# Circlez8a.net
KiCad netlist of a schematic drawn in EAGLE
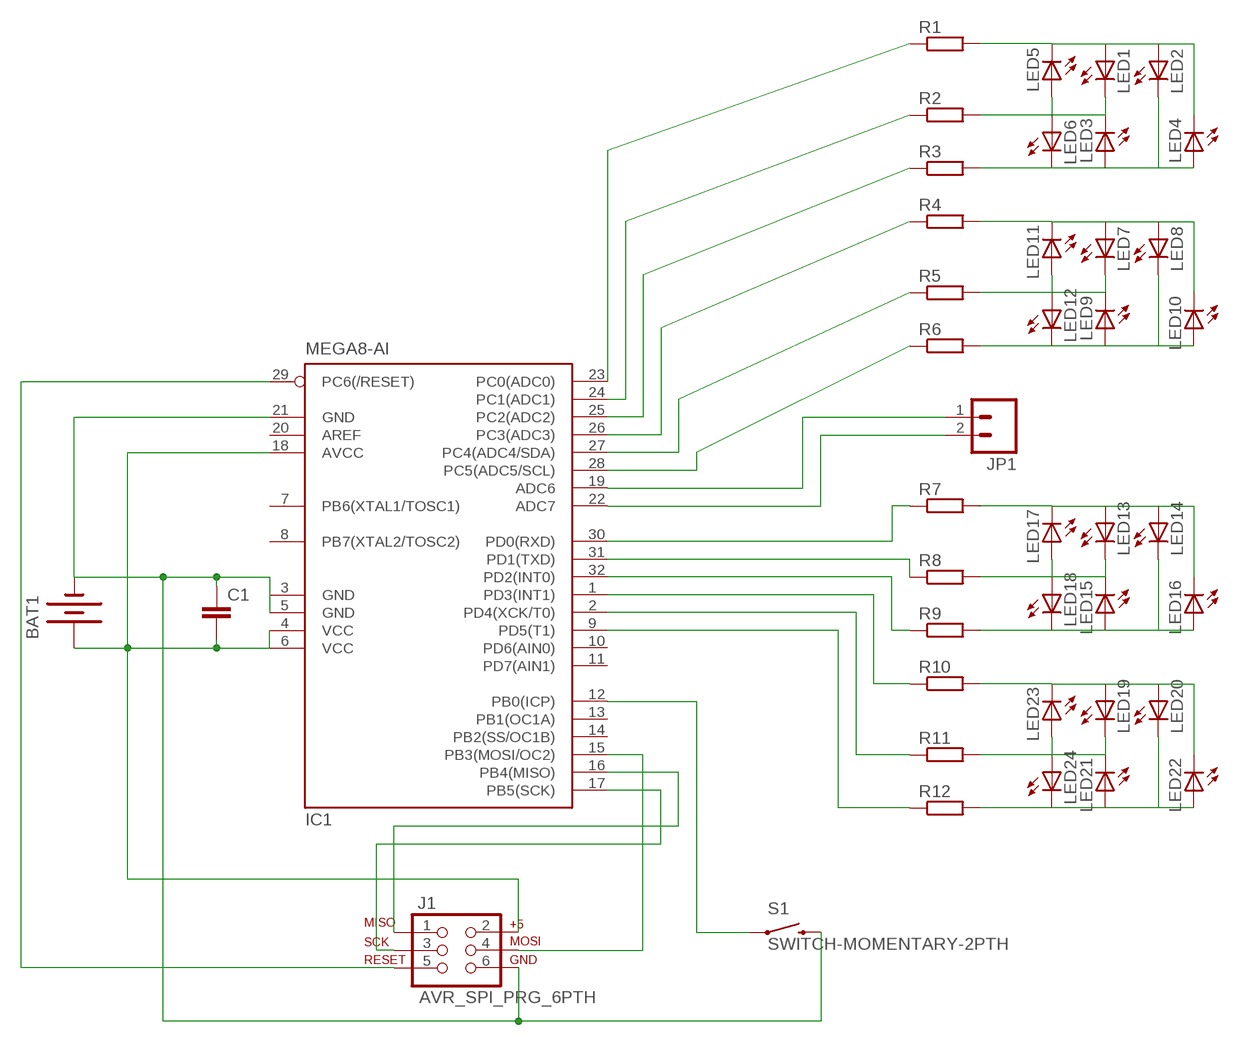
[diagram p0: schematic, sheet 1]

(export (version "E")
  (design (tool "Eeschema 10.0.6"))
  (components
    (comp (ref "BAT1")
      (value "BATTERY20PTH")
      (footprint "eagle-import:BATTCOM_20MM_PTH")
      (libsource (lib "eagle-import") (part "BATTERY20PTH"))
    )
    (comp (ref "C1")
      (value "C-EU025-024X044")
      (footprint "eagle-import:C025-024X044")
      (libsource (lib "eagle-import") (part "C-EU025-024X044"))
    )
    (comp (ref "IC1")
      (value "MEGA8-AI")
      (footprint "eagle-import:TQFP32-08")
      (fields (field (name "MPN") "ATMEGA8-16AU"))
      (libsource (lib "eagle-import") (part "MEGA8-AI"))
    )
    (comp (ref "J1")
      (value "AVR_SPI_PRG_6PTH")
      (footprint "eagle-import:2X3")
      (libsource (lib "eagle-import") (part "AVR_SPI_PRG_6PTH"))
    )
    (comp (ref "JP1")
      (value "M02PTH")
      (footprint "eagle-import:1X02")
      (libsource (lib "eagle-import") (part "M02PTH"))
    )
    (comp (ref "LED1")
      (value "LEDCHIPLED_0603")
      (footprint "eagle-import:CHIPLED_0603")
      (libsource (lib "eagle-import") (part "LEDCHIPLED_0603"))
    )
    (comp (ref "LED2")
      (value "LEDCHIPLED_0603")
      (footprint "eagle-import:CHIPLED_0603")
      (libsource (lib "eagle-import") (part "LEDCHIPLED_0603"))
    )
    (comp (ref "LED3")
      (value "LEDCHIPLED_0603")
      (footprint "eagle-import:CHIPLED_0603")
      (libsource (lib "eagle-import") (part "LEDCHIPLED_0603"))
    )
    (comp (ref "LED4")
      (value "LEDCHIPLED_0603")
      (footprint "eagle-import:CHIPLED_0603")
      (libsource (lib "eagle-import") (part "LEDCHIPLED_0603"))
    )
    (comp (ref "LED5")
      (value "LEDCHIPLED_0603")
      (footprint "eagle-import:CHIPLED_0603")
      (libsource (lib "eagle-import") (part "LEDCHIPLED_0603"))
    )
    (comp (ref "LED6")
      (value "LEDCHIPLED_0603")
      (footprint "eagle-import:CHIPLED_0603")
      (libsource (lib "eagle-import") (part "LEDCHIPLED_0603"))
    )
    (comp (ref "LED7")
      (value "LEDCHIPLED_0603")
      (footprint "eagle-import:CHIPLED_0603")
      (libsource (lib "eagle-import") (part "LEDCHIPLED_0603"))
    )
    (comp (ref "LED8")
      (value "LEDCHIPLED_0603")
      (footprint "eagle-import:CHIPLED_0603")
      (libsource (lib "eagle-import") (part "LEDCHIPLED_0603"))
    )
    (comp (ref "LED9")
      (value "LEDCHIPLED_0603")
      (footprint "eagle-import:CHIPLED_0603")
      (libsource (lib "eagle-import") (part "LEDCHIPLED_0603"))
    )
    (comp (ref "LED10")
      (value "LEDCHIPLED_0603")
      (footprint "eagle-import:CHIPLED_0603")
      (libsource (lib "eagle-import") (part "LEDCHIPLED_0603"))
    )
    (comp (ref "LED11")
      (value "LEDCHIPLED_0603")
      (footprint "eagle-import:CHIPLED_0603")
      (libsource (lib "eagle-import") (part "LEDCHIPLED_0603"))
    )
    (comp (ref "LED12")
      (value "LEDCHIPLED_0603")
      (footprint "eagle-import:CHIPLED_0603")
      (libsource (lib "eagle-import") (part "LEDCHIPLED_0603"))
    )
    (comp (ref "LED13")
      (value "LEDCHIPLED_0603")
      (footprint "eagle-import:CHIPLED_0603")
      (libsource (lib "eagle-import") (part "LEDCHIPLED_0603"))
    )
    (comp (ref "LED14")
      (value "LEDCHIPLED_0603")
      (footprint "eagle-import:CHIPLED_0603")
      (libsource (lib "eagle-import") (part "LEDCHIPLED_0603"))
    )
    (comp (ref "LED15")
      (value "LEDCHIPLED_0603")
      (footprint "eagle-import:CHIPLED_0603")
      (libsource (lib "eagle-import") (part "LEDCHIPLED_0603"))
    )
    (comp (ref "LED16")
      (value "LEDCHIPLED_0603")
      (footprint "eagle-import:CHIPLED_0603")
      (libsource (lib "eagle-import") (part "LEDCHIPLED_0603"))
    )
    (comp (ref "LED17")
      (value "LEDCHIPLED_0603")
      (footprint "eagle-import:CHIPLED_0603")
      (libsource (lib "eagle-import") (part "LEDCHIPLED_0603"))
    )
    (comp (ref "LED18")
      (value "LEDCHIPLED_0603")
      (footprint "eagle-import:CHIPLED_0603")
      (libsource (lib "eagle-import") (part "LEDCHIPLED_0603"))
    )
    (comp (ref "LED19")
      (value "LEDCHIPLED_0603")
      (footprint "eagle-import:CHIPLED_0603")
      (libsource (lib "eagle-import") (part "LEDCHIPLED_0603"))
    )
    (comp (ref "LED20")
      (value "LEDCHIPLED_0603")
      (footprint "eagle-import:CHIPLED_0603")
      (libsource (lib "eagle-import") (part "LEDCHIPLED_0603"))
    )
    (comp (ref "LED21")
      (value "LEDCHIPLED_0603")
      (footprint "eagle-import:CHIPLED_0603")
      (libsource (lib "eagle-import") (part "LEDCHIPLED_0603"))
    )
    (comp (ref "LED22")
      (value "LEDCHIPLED_0603")
      (footprint "eagle-import:CHIPLED_0603")
      (libsource (lib "eagle-import") (part "LEDCHIPLED_0603"))
    )
    (comp (ref "LED23")
      (value "LEDCHIPLED_0603")
      (footprint "eagle-import:CHIPLED_0603")
      (libsource (lib "eagle-import") (part "LEDCHIPLED_0603"))
    )
    (comp (ref "LED24")
      (value "LEDCHIPLED_0603")
      (footprint "eagle-import:CHIPLED_0603")
      (libsource (lib "eagle-import") (part "LEDCHIPLED_0603"))
    )
    (comp (ref "R1")
      (value "R-EU_R1206")
      (footprint "eagle-import:R1206")
      (libsource (lib "eagle-import") (part "R-EU_R1206"))
    )
    (comp (ref "R2")
      (value "R-EU_R1206")
      (footprint "eagle-import:R1206")
      (libsource (lib "eagle-import") (part "R-EU_R1206"))
    )
    (comp (ref "R3")
      (value "R-EU_R1206")
      (footprint "eagle-import:R1206")
      (libsource (lib "eagle-import") (part "R-EU_R1206"))
    )
    (comp (ref "R4")
      (value "R-EU_R1206")
      (footprint "eagle-import:R1206")
      (libsource (lib "eagle-import") (part "R-EU_R1206"))
    )
    (comp (ref "R5")
      (value "R-EU_R1206")
      (footprint "eagle-import:R1206")
      (libsource (lib "eagle-import") (part "R-EU_R1206"))
    )
    (comp (ref "R6")
      (value "R-EU_R1206")
      (footprint "eagle-import:R1206")
      (libsource (lib "eagle-import") (part "R-EU_R1206"))
    )
    (comp (ref "R7")
      (value "R-EU_R1206")
      (footprint "eagle-import:R1206")
      (libsource (lib "eagle-import") (part "R-EU_R1206"))
    )
    (comp (ref "R8")
      (value "R-EU_R1206")
      (footprint "eagle-import:R1206")
      (libsource (lib "eagle-import") (part "R-EU_R1206"))
    )
    (comp (ref "R9")
      (value "R-EU_R1206")
      (footprint "eagle-import:R1206")
      (libsource (lib "eagle-import") (part "R-EU_R1206"))
    )
    (comp (ref "R10")
      (value "R-EU_R1206")
      (footprint "eagle-import:R1206")
      (libsource (lib "eagle-import") (part "R-EU_R1206"))
    )
    (comp (ref "R11")
      (value "R-EU_R1206")
      (footprint "eagle-import:R1206")
      (libsource (lib "eagle-import") (part "R-EU_R1206"))
    )
    (comp (ref "R12")
      (value "R-EU_R1206")
      (footprint "eagle-import:R1206")
      (libsource (lib "eagle-import") (part "R-EU_R1206"))
    )
    (comp (ref "S1")
      (value "SWITCH-MOMENTARY-2PTH")
      (footprint "eagle-import:TACTILE-PTH")
      (libsource (lib "eagle-import") (part "SWITCH-MOMENTARY-2PTH"))
    )
  )
  (nets
    (net (code "1") (name "Net-(BAT1-+)") (class "Default")
      (node (ref "BAT1") (pin "1") (pinfunction "+_1") (pintype "power_in"))
      (node (ref "C1") (pin "2") (pinfunction "2_2") (pintype "passive"))
      (node (ref "IC1") (pin "18") (pinfunction "AVCC_18") (pintype "power_in"))
      (node (ref "IC1") (pin "4") (pinfunction "VCC_4") (pintype "power_in"))
      (node (ref "IC1") (pin "6") (pinfunction "VCC_6") (pintype "power_in"))
      (node (ref "J1") (pin "2") (pinfunction "2_2") (pintype "passive"))
    )
    (net (code "2") (name "Net-(BAT1--)") (class "Default")
      (node (ref "BAT1") (pin "2") (pinfunction "-_2") (pintype "power_in"))
      (node (ref "C1") (pin "1") (pinfunction "1_1") (pintype "passive"))
      (node (ref "IC1") (pin "21") (pinfunction "GND_21") (pintype "power_in"))
      (node (ref "IC1") (pin "3") (pinfunction "GND_3") (pintype "power_in"))
      (node (ref "IC1") (pin "5") (pinfunction "GND_5") (pintype "power_in"))
      (node (ref "J1") (pin "6") (pinfunction "6_6") (pintype "passive"))
      (node (ref "S1") (pin "3") (pinfunction "2_3") (pintype "passive"))
    )
    (net (code "3") (name "Net-(IC1-ADC6)") (class "Default")
      (node (ref "IC1") (pin "19") (pinfunction "ADC6_19") (pintype "bidirectional"))
      (node (ref "JP1") (pin "1") (pinfunction "1_1") (pintype "passive"))
    )
    (net (code "4") (name "Net-(IC1-ADC7)") (class "Default")
      (node (ref "IC1") (pin "22") (pinfunction "ADC7_22") (pintype "bidirectional"))
      (node (ref "JP1") (pin "2") (pinfunction "2_2") (pintype "passive"))
    )
    (net (code "5") (name "Net-(IC1-PB0(ICP))") (class "Default")
      (node (ref "IC1") (pin "12") (pinfunction "PB0(ICP)_12") (pintype "bidirectional"))
      (node (ref "S1") (pin "1") (pinfunction "1_1") (pintype "passive"))
    )
    (net (code "6") (name "Net-(IC1-PB3(MOSI{slash}OC2))") (class "Default")
      (node (ref "IC1") (pin "15") (pinfunction "PB3(MOSI/OC2)_15") (pintype "bidirectional"))
      (node (ref "J1") (pin "4") (pinfunction "4_4") (pintype "passive"))
    )
    (net (code "7") (name "Net-(IC1-PB4(MISO))") (class "Default")
      (node (ref "IC1") (pin "16") (pinfunction "PB4(MISO)_16") (pintype "bidirectional"))
      (node (ref "J1") (pin "1") (pinfunction "1_1") (pintype "passive"))
    )
    (net (code "8") (name "Net-(IC1-PB5(SCK))") (class "Default")
      (node (ref "IC1") (pin "17") (pinfunction "PB5(SCK)_17") (pintype "bidirectional"))
      (node (ref "J1") (pin "3") (pinfunction "3_3") (pintype "passive"))
    )
    (net (code "9") (name "Net-(IC1-PC0(ADC0))") (class "Default")
      (node (ref "IC1") (pin "23") (pinfunction "PC0(ADC0)_23") (pintype "bidirectional"))
      (node (ref "R1") (pin "1") (pinfunction "1_1") (pintype "passive"))
    )
    (net (code "10") (name "Net-(IC1-PC1(ADC1))") (class "Default")
      (node (ref "IC1") (pin "24") (pinfunction "PC1(ADC1)_24") (pintype "bidirectional"))
      (node (ref "R2") (pin "1") (pinfunction "1_1") (pintype "passive"))
    )
    (net (code "11") (name "Net-(IC1-PC2(ADC2))") (class "Default")
      (node (ref "IC1") (pin "25") (pinfunction "PC2(ADC2)_25") (pintype "bidirectional"))
      (node (ref "R3") (pin "1") (pinfunction "1_1") (pintype "passive"))
    )
    (net (code "12") (name "Net-(IC1-PC3(ADC3))") (class "Default")
      (node (ref "IC1") (pin "26") (pinfunction "PC3(ADC3)_26") (pintype "bidirectional"))
      (node (ref "R4") (pin "1") (pinfunction "1_1") (pintype "passive"))
    )
    (net (code "13") (name "Net-(IC1-PC4(ADC4{slash}SDA))") (class "Default")
      (node (ref "IC1") (pin "27") (pinfunction "PC4(ADC4/SDA)_27") (pintype "bidirectional"))
      (node (ref "R5") (pin "1") (pinfunction "1_1") (pintype "passive"))
    )
    (net (code "14") (name "Net-(IC1-PC5(ADC5{slash}SCL))") (class "Default")
      (node (ref "IC1") (pin "28") (pinfunction "PC5(ADC5/SCL)_28") (pintype "bidirectional"))
      (node (ref "R6") (pin "1") (pinfunction "1_1") (pintype "passive"))
    )
    (net (code "15") (name "Net-(IC1-PC6({slash}RESET))") (class "Default")
      (node (ref "IC1") (pin "29") (pinfunction "PC6(/RESET)_29") (pintype "bidirectional"))
      (node (ref "J1") (pin "5") (pinfunction "5_5") (pintype "passive"))
    )
    (net (code "16") (name "Net-(IC1-PD0(RXD))") (class "Default")
      (node (ref "IC1") (pin "30") (pinfunction "PD0(RXD)_30") (pintype "bidirectional"))
      (node (ref "R7") (pin "1") (pinfunction "1_1") (pintype "passive"))
    )
    (net (code "17") (name "Net-(IC1-PD1(TXD))") (class "Default")
      (node (ref "IC1") (pin "31") (pinfunction "PD1(TXD)_31") (pintype "bidirectional"))
      (node (ref "R8") (pin "1") (pinfunction "1_1") (pintype "passive"))
    )
    (net (code "18") (name "Net-(IC1-PD2(INT0))") (class "Default")
      (node (ref "IC1") (pin "32") (pinfunction "PD2(INT0)_32") (pintype "bidirectional"))
      (node (ref "R9") (pin "1") (pinfunction "1_1") (pintype "passive"))
    )
    (net (code "19") (name "Net-(IC1-PD3(INT1))") (class "Default")
      (node (ref "IC1") (pin "1") (pinfunction "PD3(INT1)_1") (pintype "bidirectional"))
      (node (ref "R10") (pin "1") (pinfunction "1_1") (pintype "passive"))
    )
    (net (code "20") (name "Net-(IC1-PD4(XCK{slash}T0))") (class "Default")
      (node (ref "IC1") (pin "2") (pinfunction "PD4(XCK/T0)_2") (pintype "bidirectional"))
      (node (ref "R11") (pin "1") (pinfunction "1_1") (pintype "passive"))
    )
    (net (code "21") (name "Net-(IC1-PD5(T1))") (class "Default")
      (node (ref "IC1") (pin "9") (pinfunction "PD5(T1)_9") (pintype "bidirectional"))
      (node (ref "R12") (pin "1") (pinfunction "1_1") (pintype "passive"))
    )
    (net (code "22") (name "Net-(LED1-PadA)") (class "Default")
      (node (ref "LED1") (pin "A") (pinfunction "A_A") (pintype "passive"))
      (node (ref "LED2") (pin "A") (pinfunction "A_A") (pintype "passive"))
      (node (ref "LED4") (pin "C") (pinfunction "C_C") (pintype "passive"))
      (node (ref "LED5") (pin "C") (pinfunction "C_C") (pintype "passive"))
      (node (ref "R1") (pin "2") (pinfunction "2_2") (pintype "passive"))
    )
    (net (code "23") (name "Net-(LED1-PadC)") (class "Default")
      (node (ref "LED1") (pin "C") (pinfunction "C_C") (pintype "passive"))
      (node (ref "LED3") (pin "C") (pinfunction "C_C") (pintype "passive"))
      (node (ref "LED5") (pin "A") (pinfunction "A_A") (pintype "passive"))
      (node (ref "LED6") (pin "A") (pinfunction "A_A") (pintype "passive"))
      (node (ref "R2") (pin "2") (pinfunction "2_2") (pintype "passive"))
    )
    (net (code "24") (name "Net-(LED2-PadC)") (class "Default")
      (node (ref "LED2") (pin "C") (pinfunction "C_C") (pintype "passive"))
      (node (ref "LED3") (pin "A") (pinfunction "A_A") (pintype "passive"))
      (node (ref "LED4") (pin "A") (pinfunction "A_A") (pintype "passive"))
      (node (ref "LED6") (pin "C") (pinfunction "C_C") (pintype "passive"))
      (node (ref "R3") (pin "2") (pinfunction "2_2") (pintype "passive"))
    )
    (net (code "25") (name "Net-(LED10-PadA)") (class "Default")
      (node (ref "LED10") (pin "A") (pinfunction "A_A") (pintype "passive"))
      (node (ref "LED12") (pin "C") (pinfunction "C_C") (pintype "passive"))
      (node (ref "LED8") (pin "C") (pinfunction "C_C") (pintype "passive"))
      (node (ref "LED9") (pin "A") (pinfunction "A_A") (pintype "passive"))
      (node (ref "R6") (pin "2") (pinfunction "2_2") (pintype "passive"))
    )
    (net (code "26") (name "Net-(LED10-PadC)") (class "Default")
      (node (ref "LED10") (pin "C") (pinfunction "C_C") (pintype "passive"))
      (node (ref "LED11") (pin "C") (pinfunction "C_C") (pintype "passive"))
      (node (ref "LED7") (pin "A") (pinfunction "A_A") (pintype "passive"))
      (node (ref "LED8") (pin "A") (pinfunction "A_A") (pintype "passive"))
      (node (ref "R4") (pin "2") (pinfunction "2_2") (pintype "passive"))
    )
    (net (code "27") (name "Net-(LED11-PadA)") (class "Default")
      (node (ref "LED11") (pin "A") (pinfunction "A_A") (pintype "passive"))
      (node (ref "LED12") (pin "A") (pinfunction "A_A") (pintype "passive"))
      (node (ref "LED7") (pin "C") (pinfunction "C_C") (pintype "passive"))
      (node (ref "LED9") (pin "C") (pinfunction "C_C") (pintype "passive"))
      (node (ref "R5") (pin "2") (pinfunction "2_2") (pintype "passive"))
    )
    (net (code "28") (name "Net-(LED13-PadA)") (class "Default")
      (node (ref "LED13") (pin "A") (pinfunction "A_A") (pintype "passive"))
      (node (ref "LED14") (pin "A") (pinfunction "A_A") (pintype "passive"))
      (node (ref "LED16") (pin "C") (pinfunction "C_C") (pintype "passive"))
      (node (ref "LED17") (pin "C") (pinfunction "C_C") (pintype "passive"))
      (node (ref "R7") (pin "2") (pinfunction "2_2") (pintype "passive"))
    )
    (net (code "29") (name "Net-(LED13-PadC)") (class "Default")
      (node (ref "LED13") (pin "C") (pinfunction "C_C") (pintype "passive"))
      (node (ref "LED15") (pin "C") (pinfunction "C_C") (pintype "passive"))
      (node (ref "LED17") (pin "A") (pinfunction "A_A") (pintype "passive"))
      (node (ref "LED18") (pin "A") (pinfunction "A_A") (pintype "passive"))
      (node (ref "R8") (pin "2") (pinfunction "2_2") (pintype "passive"))
    )
    (net (code "30") (name "Net-(LED14-PadC)") (class "Default")
      (node (ref "LED14") (pin "C") (pinfunction "C_C") (pintype "passive"))
      (node (ref "LED15") (pin "A") (pinfunction "A_A") (pintype "passive"))
      (node (ref "LED16") (pin "A") (pinfunction "A_A") (pintype "passive"))
      (node (ref "LED18") (pin "C") (pinfunction "C_C") (pintype "passive"))
      (node (ref "R9") (pin "2") (pinfunction "2_2") (pintype "passive"))
    )
    (net (code "31") (name "Net-(LED19-PadA)") (class "Default")
      (node (ref "LED19") (pin "A") (pinfunction "A_A") (pintype "passive"))
      (node (ref "LED20") (pin "A") (pinfunction "A_A") (pintype "passive"))
      (node (ref "LED22") (pin "C") (pinfunction "C_C") (pintype "passive"))
      (node (ref "LED23") (pin "C") (pinfunction "C_C") (pintype "passive"))
      (node (ref "R10") (pin "2") (pinfunction "2_2") (pintype "passive"))
    )
    (net (code "32") (name "Net-(LED19-PadC)") (class "Default")
      (node (ref "LED19") (pin "C") (pinfunction "C_C") (pintype "passive"))
      (node (ref "LED21") (pin "C") (pinfunction "C_C") (pintype "passive"))
      (node (ref "LED23") (pin "A") (pinfunction "A_A") (pintype "passive"))
      (node (ref "LED24") (pin "A") (pinfunction "A_A") (pintype "passive"))
      (node (ref "R11") (pin "2") (pinfunction "2_2") (pintype "passive"))
    )
    (net (code "33") (name "Net-(LED20-PadC)") (class "Default")
      (node (ref "LED20") (pin "C") (pinfunction "C_C") (pintype "passive"))
      (node (ref "LED21") (pin "A") (pinfunction "A_A") (pintype "passive"))
      (node (ref "LED22") (pin "A") (pinfunction "A_A") (pintype "passive"))
      (node (ref "LED24") (pin "C") (pinfunction "C_C") (pintype "passive"))
      (node (ref "R12") (pin "2") (pinfunction "2_2") (pintype "passive"))
    )
    (net (code "34") (name "unconnected-(IC1-AREF-Pad20)") (class "Default")
      (node (ref "IC1") (pin "20") (pinfunction "AREF_20") (pintype "passive"))
    )
    (net (code "35") (name "unconnected-(IC1-PB1(OC1A)-Pad13)") (class "Default")
      (node (ref "IC1") (pin "13") (pinfunction "PB1(OC1A)_13") (pintype "bidirectional"))
    )
    (net (code "36") (name "unconnected-(IC1-PB2(SS{slash}OC1B)-Pad14)") (class "Default")
      (node (ref "IC1") (pin "14") (pinfunction "PB2(SS/OC1B)_14") (pintype "bidirectional"))
    )
    (net (code "37") (name "unconnected-(IC1-PB6(XTAL1{slash}TOSC1)-Pad7)") (class "Default")
      (node (ref "IC1") (pin "7") (pinfunction "PB6(XTAL1/TOSC1)_7") (pintype "bidirectional"))
    )
    (net (code "38") (name "unconnected-(IC1-PB7(XTAL2{slash}TOSC2)-Pad8)") (class "Default")
      (node (ref "IC1") (pin "8") (pinfunction "PB7(XTAL2/TOSC2)_8") (pintype "bidirectional"))
    )
    (net (code "39") (name "unconnected-(IC1-PD6(AIN0)-Pad10)") (class "Default")
      (node (ref "IC1") (pin "10") (pinfunction "PD6(AIN0)_10") (pintype "bidirectional"))
    )
    (net (code "40") (name "unconnected-(IC1-PD7(AIN1)-Pad11)") (class "Default")
      (node (ref "IC1") (pin "11") (pinfunction "PD7(AIN1)_11") (pintype "bidirectional"))
    )
  )
)
